# Adafruit_MicroUSB_Lipo.net
KiCad netlist of a schematic drawn in EAGLE
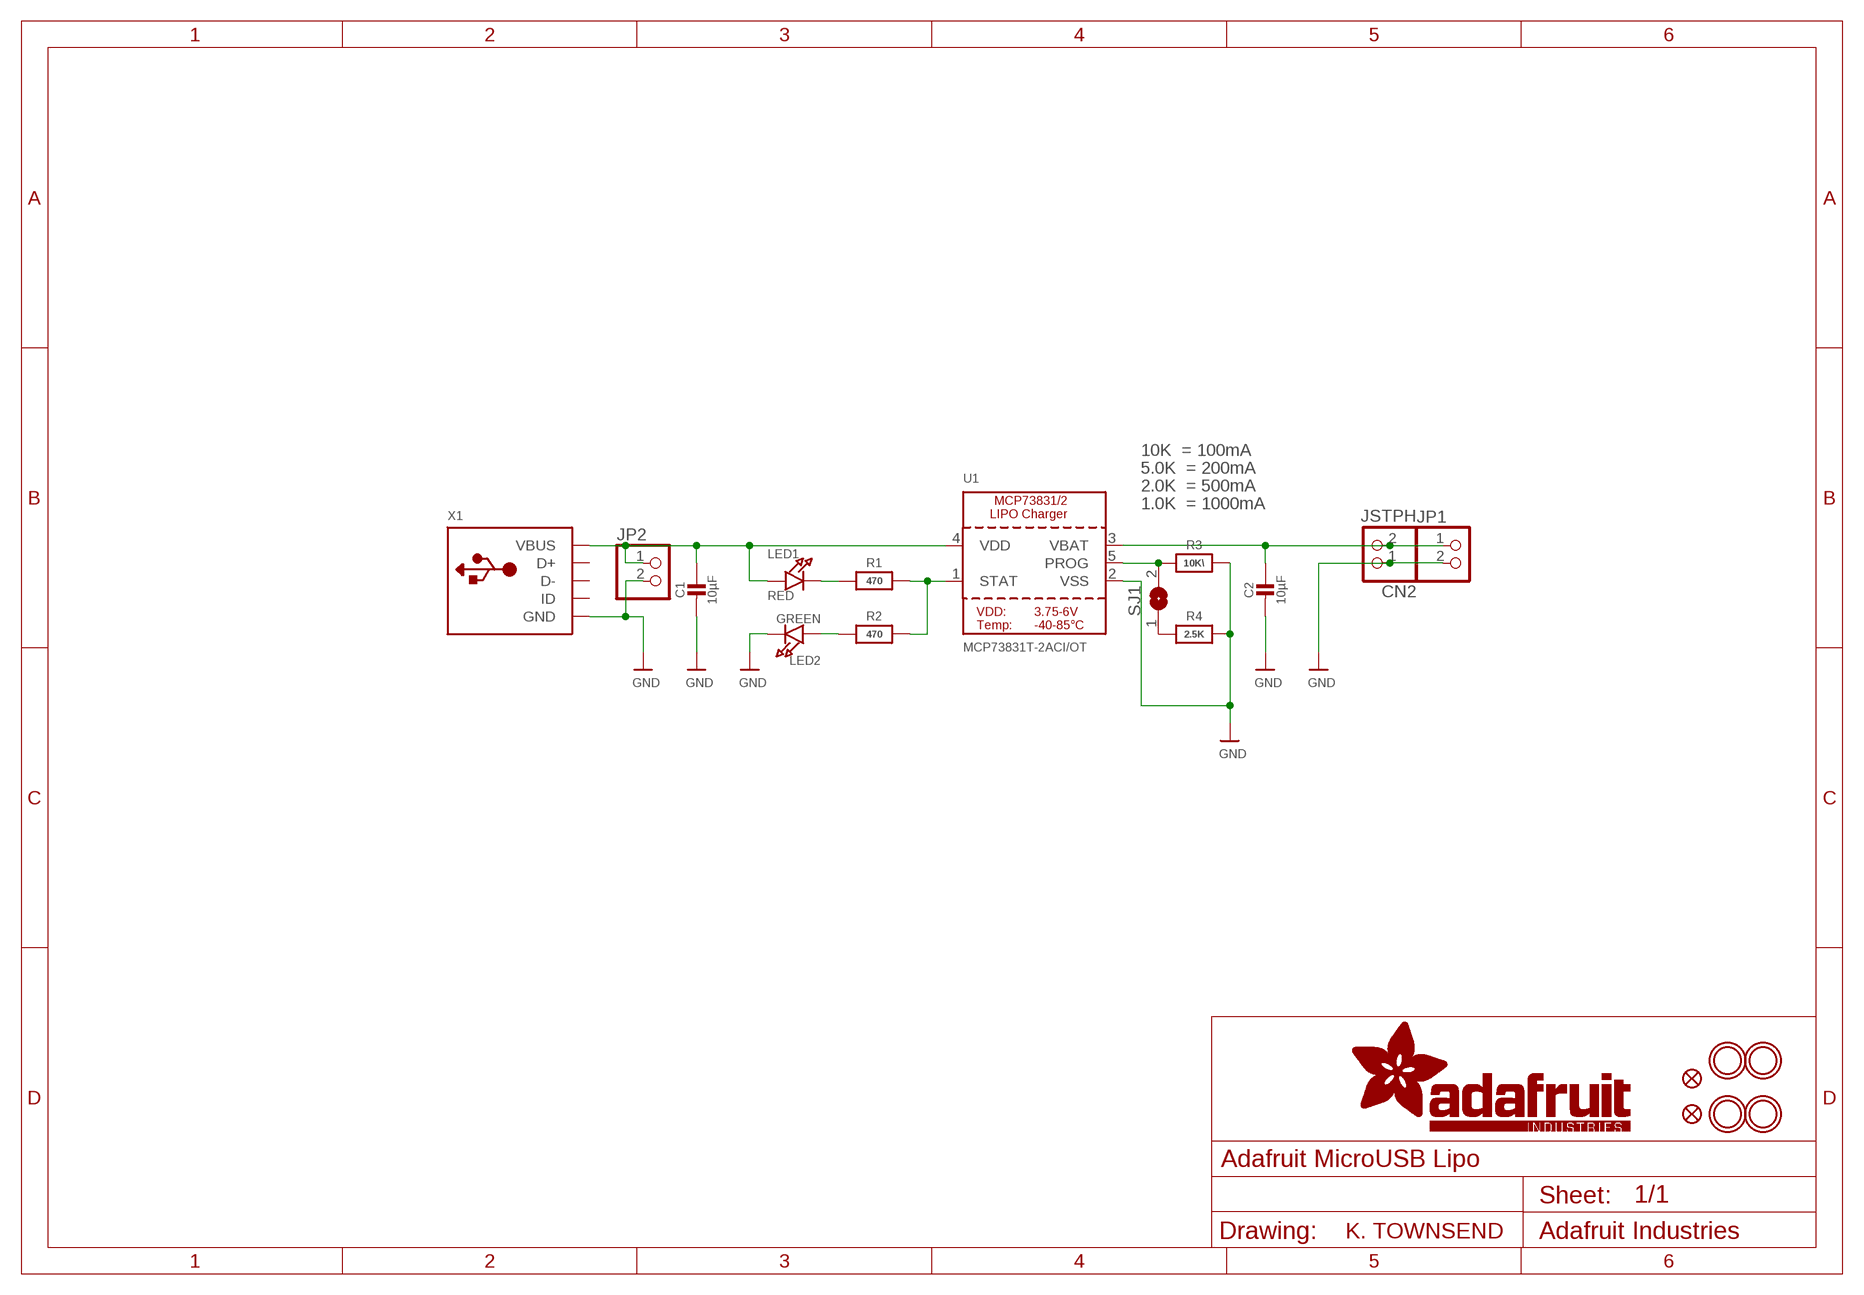
[diagram p0: schematic, sheet 1]

(export (version "E")
  (design (tool "Eeschema 10.0.6"))
  (components
    (comp (ref "C1")
      (value "10µF")
      (footprint "eagle-import:0805-NO")
      (libsource (lib "eagle-import") (part "CAP_CERAMIC0805-NOOUTLINE"))
    )
    (comp (ref "C2")
      (value "10µF")
      (footprint "eagle-import:0805-NO")
      (libsource (lib "eagle-import") (part "CAP_CERAMIC0805-NOOUTLINE"))
    )
    (comp (ref "CN2")
      (value "JSTPH")
      (footprint "eagle-import:JSTPH2")
      (libsource (lib "eagle-import") (part "JST_2PIN"))
    )
    (comp (ref "FID1")
      (value "FIDUCIAL\"\"")
      (footprint "eagle-import:FIDUCIAL_1MM")
      (libsource (lib "eagle-import") (part "FIDUCIAL{dblquote}{dblquote}"))
    )
    (comp (ref "FID2")
      (value "FIDUCIAL\"\"")
      (footprint "eagle-import:FIDUCIAL_1MM")
      (fields (field (name "BOM") "EXCLUDE"))
      (libsource (lib "eagle-import") (part "FIDUCIAL{dblquote}{dblquote}"))
    )
    (comp (ref "JP1")
      (value "HEADER-1X2ROUND")
      (footprint "eagle-import:1X02_ROUND")
      (libsource (lib "eagle-import") (part "HEADER-1X2ROUND"))
    )
    (comp (ref "JP2")
      (value "HEADER-1X2ROUND")
      (footprint "eagle-import:1X02_ROUND")
      (libsource (lib "eagle-import") (part "HEADER-1X2ROUND"))
    )
    (comp (ref "LED1")
      (value "RED")
      (footprint "eagle-import:CHIPLED_0805_NOOUTLINE")
      (libsource (lib "eagle-import") (part "LED0805_NOOUTLINE"))
    )
    (comp (ref "LED2")
      (value "GREEN")
      (footprint "eagle-import:CHIPLED_0805_NOOUTLINE")
      (libsource (lib "eagle-import") (part "LED0805_NOOUTLINE"))
    )
    (comp (ref "R1")
      (value "470")
      (footprint "eagle-import:0805-NO")
      (libsource (lib "eagle-import") (part "RESISTOR0805_NOOUTLINE"))
    )
    (comp (ref "R2")
      (value "470")
      (footprint "eagle-import:0805-NO")
      (libsource (lib "eagle-import") (part "RESISTOR0805_NOOUTLINE"))
    )
    (comp (ref "R3")
      (value "10K\\")
      (footprint "eagle-import:0805-NO")
      (libsource (lib "eagle-import") (part "RESISTOR0805_NOOUTLINE"))
    )
    (comp (ref "R4")
      (value "2.5K")
      (footprint "eagle-import:0805-NO")
      (libsource (lib "eagle-import") (part "RESISTOR0805_NOOUTLINE"))
    )
    (comp (ref "SJ1")
      (value "SOLDERJUMPER")
      (footprint "eagle-import:SOLDERJUMPER_ARROW_NOPASTE")
      (libsource (lib "eagle-import") (part "SOLDERJUMPER"))
    )
    (comp (ref "U$9")
      (value "MOUNTINGHOLE2.5")
      (footprint "eagle-import:MOUNTINGHOLE_2.5_PLATED")
      (libsource (lib "eagle-import") (part "MOUNTINGHOLE2.5"))
    )
    (comp (ref "U$10")
      (value "MOUNTINGHOLE2.5")
      (footprint "eagle-import:MOUNTINGHOLE_2.5_PLATED")
      (libsource (lib "eagle-import") (part "MOUNTINGHOLE2.5"))
    )
    (comp (ref "U$11")
      (value "MOUNTINGHOLE2.5")
      (footprint "eagle-import:MOUNTINGHOLE_2.5_PLATED")
      (libsource (lib "eagle-import") (part "MOUNTINGHOLE2.5"))
    )
    (comp (ref "U$12")
      (value "MOUNTINGHOLE2.5")
      (footprint "eagle-import:MOUNTINGHOLE_2.5_PLATED")
      (libsource (lib "eagle-import") (part "MOUNTINGHOLE2.5"))
    )
    (comp (ref "U1")
      (value "MCP73831T-2ACI/OT")
      (footprint "eagle-import:SOT23-5")
      (libsource (lib "eagle-import") (part "MCP73831/2"))
    )
    (comp (ref "X1")
      (value "USBMICRO_20329")
      (footprint "eagle-import:4UCONN_20329")
      (libsource (lib "eagle-import") (part "USBMICRO_20329"))
    )
  )
  (nets
    (net (code "1") (name "GND") (class "Default")
      (node (ref "C1") (pin "2") (pinfunction "2_2") (pintype "passive"))
      (node (ref "C2") (pin "2") (pinfunction "2_2") (pintype "passive"))
      (node (ref "CN2") (pin "1") (pinfunction "1_1") (pintype "passive"))
      (node (ref "JP1") (pin "2") (pinfunction "2_2") (pintype "passive"))
      (node (ref "JP2") (pin "2") (pinfunction "2_2") (pintype "passive"))
      (node (ref "LED2") (pin "C") (pinfunction "C_C") (pintype "passive"))
      (node (ref "R3") (pin "2") (pinfunction "2_2") (pintype "passive"))
      (node (ref "R4") (pin "2") (pinfunction "2_2") (pintype "passive"))
      (node (ref "U1") (pin "2") (pinfunction "VSS_2") (pintype "power_in"))
      (node (ref "X1") (pin "BASE@1") (pinfunction "GND_BASE@1") (pintype "power_in"))
      (node (ref "X1") (pin "BASE@2") (pinfunction "GND_BASE@2") (pintype "power_in"))
      (node (ref "X1") (pin "GND") (pinfunction "GND_GND") (pintype "power_in"))
      (node (ref "X1") (pin "SPRT@1") (pinfunction "GND_SPRT@1") (pintype "power_in"))
      (node (ref "X1") (pin "SPRT@2") (pinfunction "GND_SPRT@2") (pintype "power_in"))
      (node (ref "X1") (pin "SPRT@3") (pinfunction "GND_SPRT@3") (pintype "power_in"))
      (node (ref "X1") (pin "SPRT@4") (pinfunction "GND_SPRT@4") (pintype "power_in"))
    )
    (net (code "2") (name "Net-(LED1-PadC)") (class "Default")
      (node (ref "LED1") (pin "C") (pinfunction "C_C") (pintype "passive"))
      (node (ref "R1") (pin "1") (pinfunction "1_1") (pintype "passive"))
    )
    (net (code "3") (name "Net-(LED2-PadA)") (class "Default")
      (node (ref "LED2") (pin "A") (pinfunction "A_A") (pintype "passive"))
      (node (ref "R2") (pin "1") (pinfunction "1_1") (pintype "passive"))
    )
    (net (code "4") (name "Net-(R4-Pad1)") (class "Default")
      (node (ref "R4") (pin "1") (pinfunction "1_1") (pintype "passive"))
      (node (ref "SJ1") (pin "1") (pinfunction "1_1") (pintype "passive"))
    )
    (net (code "5") (name "Net-(U1-PROG)") (class "Default")
      (node (ref "R3") (pin "1") (pinfunction "1_1") (pintype "passive"))
      (node (ref "SJ1") (pin "2") (pinfunction "2_2") (pintype "passive"))
      (node (ref "U1") (pin "5") (pinfunction "PROG_5") (pintype "input"))
    )
    (net (code "6") (name "Net-(U1-STAT)") (class "Default")
      (node (ref "R1") (pin "2") (pinfunction "2_2") (pintype "passive"))
      (node (ref "R2") (pin "2") (pinfunction "2_2") (pintype "passive"))
      (node (ref "U1") (pin "1") (pinfunction "STAT_1") (pintype "output"))
    )
    (net (code "7") (name "Net-(U1-VBAT)") (class "Default")
      (node (ref "C2") (pin "1") (pinfunction "1_1") (pintype "passive"))
      (node (ref "CN2") (pin "2") (pinfunction "2_2") (pintype "passive"))
      (node (ref "JP1") (pin "1") (pinfunction "1_1") (pintype "passive"))
      (node (ref "U1") (pin "3") (pinfunction "VBAT_3") (pintype "power_in"))
    )
    (net (code "8") (name "Net-(U1-VDD)") (class "Default")
      (node (ref "C1") (pin "1") (pinfunction "1_1") (pintype "passive"))
      (node (ref "JP2") (pin "1") (pinfunction "1_1") (pintype "passive"))
      (node (ref "LED1") (pin "A") (pinfunction "A_A") (pintype "passive"))
      (node (ref "U1") (pin "4") (pinfunction "VDD_4") (pintype "power_in"))
      (node (ref "X1") (pin "VBUS") (pinfunction "VBUS_VBUS") (pintype "power_in"))
    )
    (net (code "9") (name "unconnected-(X1-PadD+)") (class "Default")
      (node (ref "X1") (pin "D+") (pinfunction "D+_D+") (pintype "bidirectional"))
    )
    (net (code "10") (name "unconnected-(X1-PadD-)") (class "Default")
      (node (ref "X1") (pin "D-") (pinfunction "D-_D-") (pintype "bidirectional"))
    )
    (net (code "11") (name "unconnected-(X1-PadID)") (class "Default")
      (node (ref "X1") (pin "ID") (pinfunction "ID_ID") (pintype "bidirectional"))
    )
  )
)
